# Sensor_DataS.net
KiCad netlist of a schematic drawn in Altium Designer
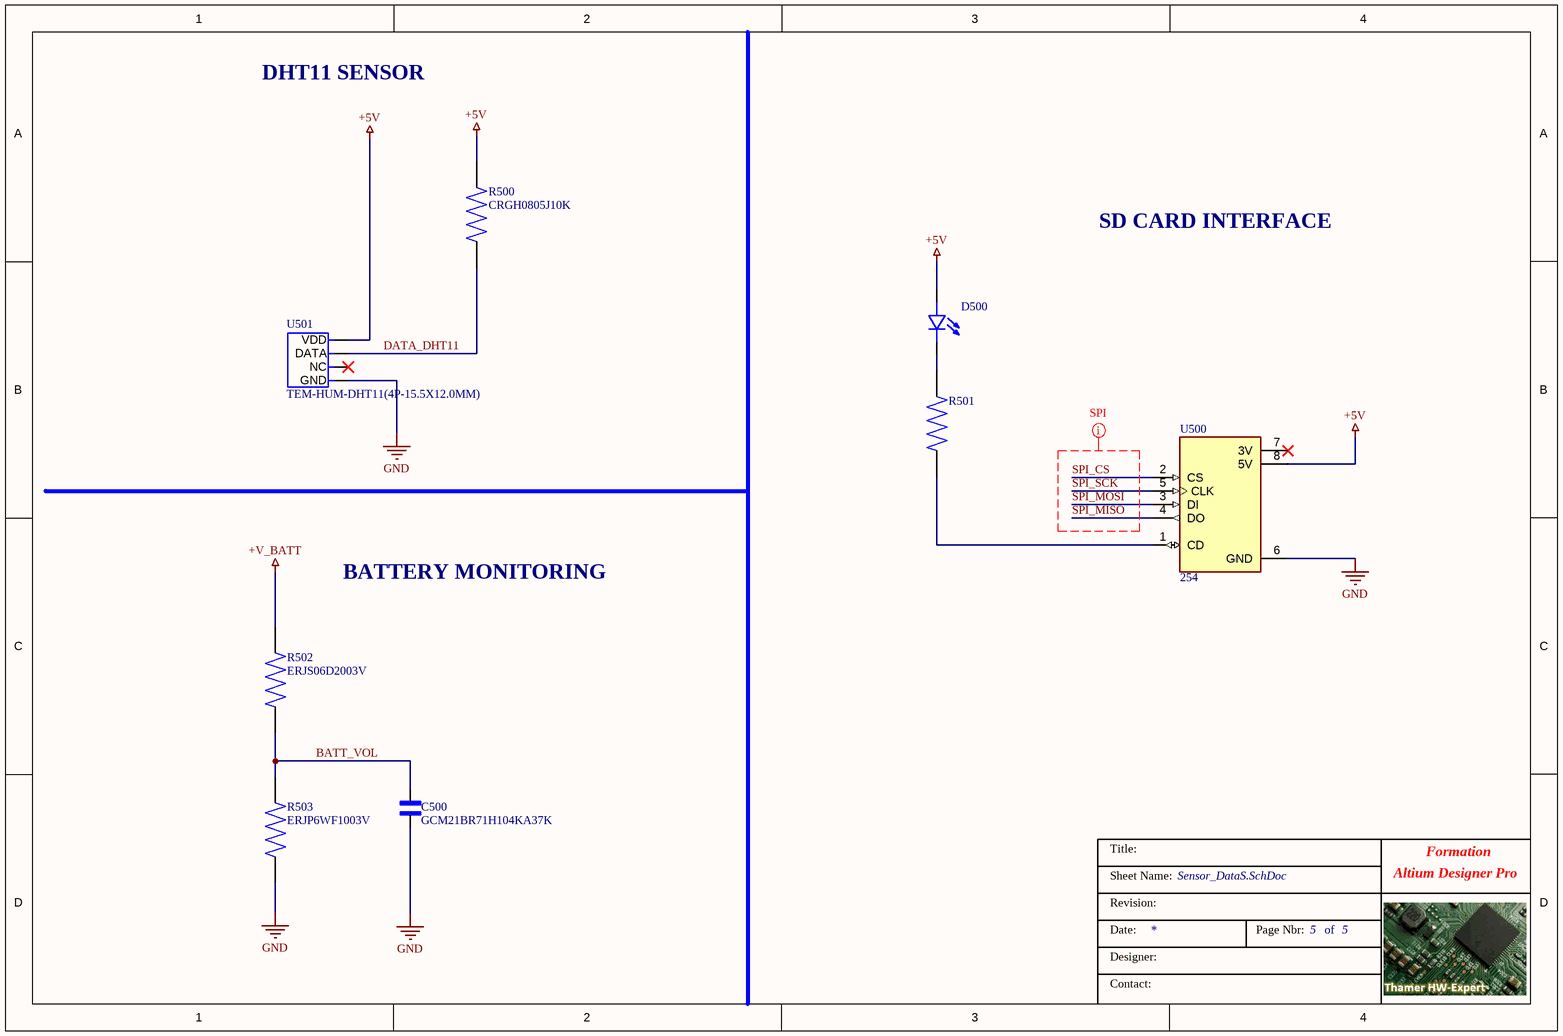
[diagram p0: Sensor_DataS.SchDoc]

(export (version "E")
  (design (tool "Eeschema 10.0.6"))
  (components
    (comp (ref "C500")
      (value "GCM21BR71H104KA37K")
      (footprint "CAPC2012X135N")
      (description ".1UF 50V 10% 080")
      (fields (field (name "MF") "{'manufacturer': u'Murata'}"))
      (libsource (lib "Capacitor") (part "GCM21BR71H104KA37K"))
    )
    (comp (ref "D500")
      (value "SML-LXT0805GW-TR")
      (footprint "LEDC2012X120N")
      (fields (field (name "MF") "{'manufacturer': u'Lumex Opto/Components'}"))
      (libsource (lib "Diode") (part "SML-LXT0805GW-TR"))
    )
    (comp (ref "R500")
      (value "CRGH0805J10K")
      (footprint "RESC2012X65N")
      (description "Res Thick Film 0805 10K Ohm 5% 1/3W Â±100ppm/Â°C Molded SMD SMD T/R")
      (fields (field (name "MF") "{'manufacturer': u'TE Connectivity'}"))
      (libsource (lib "Resistor") (part "CRGH0805J10K"))
    )
    (comp (ref "R501")
      (value "TNPW0805150RBHEA")
      (footprint "RESC2012X55N")
      (fields (field (name "MF") "{'manufacturer': u'Vishay'}"))
      (libsource (lib "Resistor") (part "TNPW0805150RBHEA"))
    )
    (comp (ref "R502")
      (value "ERJS06D2003V")
      (footprint "RES_ERJS06D2003V")
      (fields (field (name "MF") "{'manufacturer': u'Panasonic'}"))
      (libsource (lib "Resistor") (part "ERJS06D2003V"))
    )
    (comp (ref "R503")
      (value "ERJP6WF1003V")
      (footprint "RESC2012X75N")
      (description "100K OHM 1% 1/2W")
      (fields (field (name "MF") "{'manufacturer': u'Panasonic'}"))
      (libsource (lib "Resistor") (part "ERJP6WF1003V"))
    )
    (comp (ref "U500")
      (value "254")
      (footprint "MODULE_254")
      (fields (field (name "MF") "{'manufacturer': u'Adafruit'}"))
      (libsource (lib "Breakout") (part "254"))
    )
    (comp (ref "U501")
      (value "TEM-HUM-DHT11(4P-15.5X12.0MM)")
      (footprint "DHT11:SNR4-2.54-15.5X12.0X5.5MM")
      (description "314010000")
      (fields
        (field (name "MF") "{'manufacturer': u'UNIVERSAL-SOLDER Electronics Ltd'}")
        (field (name "MP") "DHT11")
      )
      (libsource (lib "*") (part "TEM-HUM-DHT11(4P-15.5X12.0MM)"))
    )
  )
  (nets
    (net (code "1") (name "+5V") (class "Default")
      (node (ref "D500") (pin "A") (pinfunction "A_A") (pintype "passive"))
      (node (ref "R500") (pin "2") (pinfunction "2_2") (pintype "passive"))
      (node (ref "U500") (pin "8") (pinfunction "5V_8") (pintype "power_in"))
      (node (ref "U501") (pin "1") (pinfunction "VDD_1") (pintype "power_in"))
    )
    (net (code "2") (name "+V_BATT") (class "Default")
      (node (ref "R502") (pin "2") (pinfunction "2_2") (pintype "passive"))
    )
    (net (code "3") (name "/BATT_VOL") (class "Default")
      (node (ref "C500") (pin "1") (pinfunction "1_1") (pintype "passive"))
      (node (ref "R502") (pin "1") (pinfunction "1_1") (pintype "passive"))
      (node (ref "R503") (pin "2") (pinfunction "2_2") (pintype "passive"))
    )
    (net (code "4") (name "/DATA_DHT11") (class "Default")
      (node (ref "R500") (pin "1") (pinfunction "1_1") (pintype "passive"))
      (node (ref "U501") (pin "2") (pinfunction "DATA_2") (pintype "bidirectional"))
    )
    (net (code "5") (name "/SPI_CS") (class "Default")
      (node (ref "U500") (pin "2") (pinfunction "CS_2") (pintype "input"))
    )
    (net (code "6") (name "/SPI_MISO") (class "Default")
      (node (ref "U500") (pin "4") (pinfunction "DO_4") (pintype "output"))
    )
    (net (code "7") (name "/SPI_MOSI") (class "Default")
      (node (ref "U500") (pin "3") (pinfunction "DI_3") (pintype "input"))
    )
    (net (code "8") (name "/SPI_SCK") (class "Default")
      (node (ref "U500") (pin "5") (pinfunction "CLK_5") (pintype "input"))
    )
    (net (code "9") (name "GND") (class "Default")
      (node (ref "C500") (pin "2") (pinfunction "2_2") (pintype "passive"))
      (node (ref "R503") (pin "1") (pinfunction "1_1") (pintype "passive"))
      (node (ref "U500") (pin "6") (pinfunction "GND_6") (pintype "power_in"))
      (node (ref "U501") (pin "4") (pinfunction "GND_4") (pintype "power_in"))
    )
    (net (code "10") (name "Net-(D500-PadC)") (class "Default")
      (node (ref "D500") (pin "C") (pinfunction "C_C") (pintype "passive"))
      (node (ref "R501") (pin "1") (pinfunction "1_1") (pintype "passive"))
    )
    (net (code "11") (name "Net-(U500-CD)") (class "Default")
      (node (ref "R501") (pin "2") (pinfunction "2_2") (pintype "passive"))
      (node (ref "U500") (pin "1") (pinfunction "CD_1") (pintype "bidirectional"))
    )
    (net (code "12") (name "unconnected-(U500-3V-Pad7)") (class "Default")
      (node (ref "U500") (pin "7") (pinfunction "3V_7") (pintype "power_in+no_connect"))
    )
    (net (code "13") (name "unconnected-(U501-NC-Pad3)") (class "Default")
      (node (ref "U501") (pin "3") (pinfunction "NC_3") (pintype "passive+no_connect"))
    )
  )
)
